# STLink-Adapter.net
KiCad netlist of a schematic drawn in EAGLE
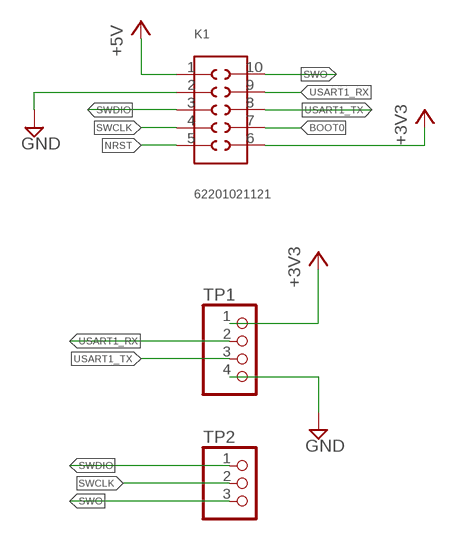
[diagram p0: schematic, sheet 1]

(export (version "E")
  (design (tool "Eeschema 10.0.6"))
  (components
    (comp (ref "K1")
      (value "62201021121")
      (footprint "eagle-import:62201021121")
      (libsource (lib "eagle-import") (part "62201021121"))
    )
    (comp (ref "TP1")
      (value "TP-1X4")
      (footprint "eagle-import:1X04")
      (libsource (lib "eagle-import") (part "TP-1X4"))
    )
    (comp (ref "TP2")
      (value "TP-1X3")
      (footprint "eagle-import:1X03")
      (libsource (lib "eagle-import") (part "TP-1X3"))
    )
  )
  (nets
    (net (code "1") (name "+3V3") (class "Default")
      (node (ref "K1") (pin "6") (pinfunction "6_6") (pintype "passive"))
      (node (ref "TP1") (pin "1") (pinfunction "1_1") (pintype "passive"))
    )
    (net (code "2") (name "+5V") (class "Default")
      (node (ref "K1") (pin "1") (pinfunction "1_1") (pintype "passive"))
    )
    (net (code "3") (name "BOOT0") (class "Default")
      (node (ref "K1") (pin "7") (pinfunction "7_7") (pintype "passive"))
    )
    (net (code "4") (name "GND") (class "Default")
      (node (ref "K1") (pin "2") (pinfunction "2_2") (pintype "passive"))
      (node (ref "TP1") (pin "4") (pinfunction "4_4") (pintype "passive"))
    )
    (net (code "5") (name "NRST") (class "Default")
      (node (ref "K1") (pin "5") (pinfunction "5_5") (pintype "passive"))
    )
    (net (code "6") (name "SWCLK") (class "Default")
      (node (ref "K1") (pin "4") (pinfunction "4_4") (pintype "passive"))
      (node (ref "TP2") (pin "2") (pinfunction "2_2") (pintype "passive"))
    )
    (net (code "7") (name "SWDIO") (class "Default")
      (node (ref "K1") (pin "3") (pinfunction "3_3") (pintype "passive"))
      (node (ref "TP2") (pin "1") (pinfunction "1_1") (pintype "passive"))
    )
    (net (code "8") (name "SWO") (class "Default")
      (node (ref "K1") (pin "10") (pinfunction "10_10") (pintype "passive"))
      (node (ref "TP2") (pin "3") (pinfunction "3_3") (pintype "passive"))
    )
    (net (code "9") (name "USART1_RX") (class "Default")
      (node (ref "K1") (pin "9") (pinfunction "9_9") (pintype "passive"))
      (node (ref "TP1") (pin "2") (pinfunction "2_2") (pintype "passive"))
    )
    (net (code "10") (name "USART1_TX") (class "Default")
      (node (ref "K1") (pin "8") (pinfunction "8_8") (pintype "passive"))
      (node (ref "TP1") (pin "3") (pinfunction "3_3") (pintype "passive"))
    )
  )
)
